# HMC1001_module.net
KiCad netlist of a schematic drawn in Altium Designer
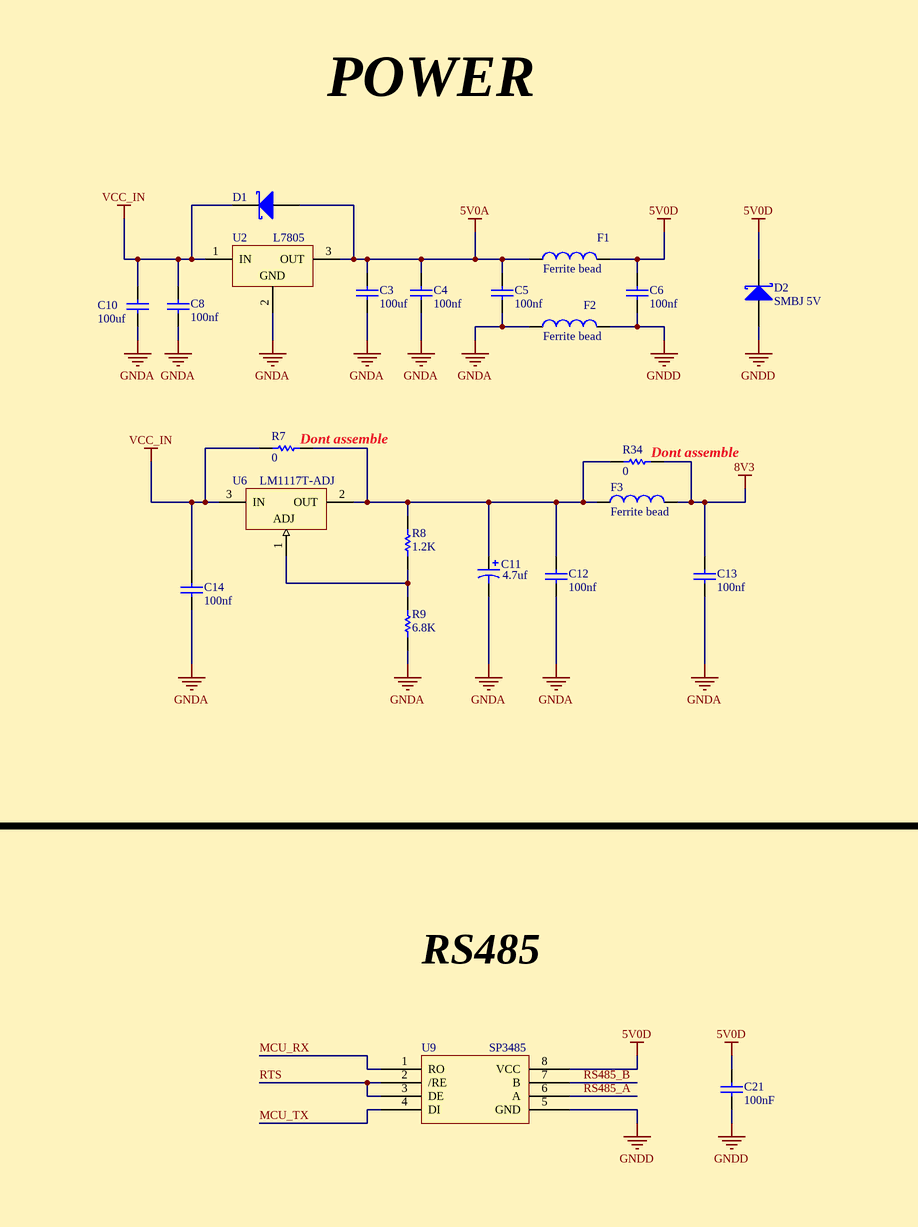
[diagram p0: HMC1001_module.SchDoc, top left]
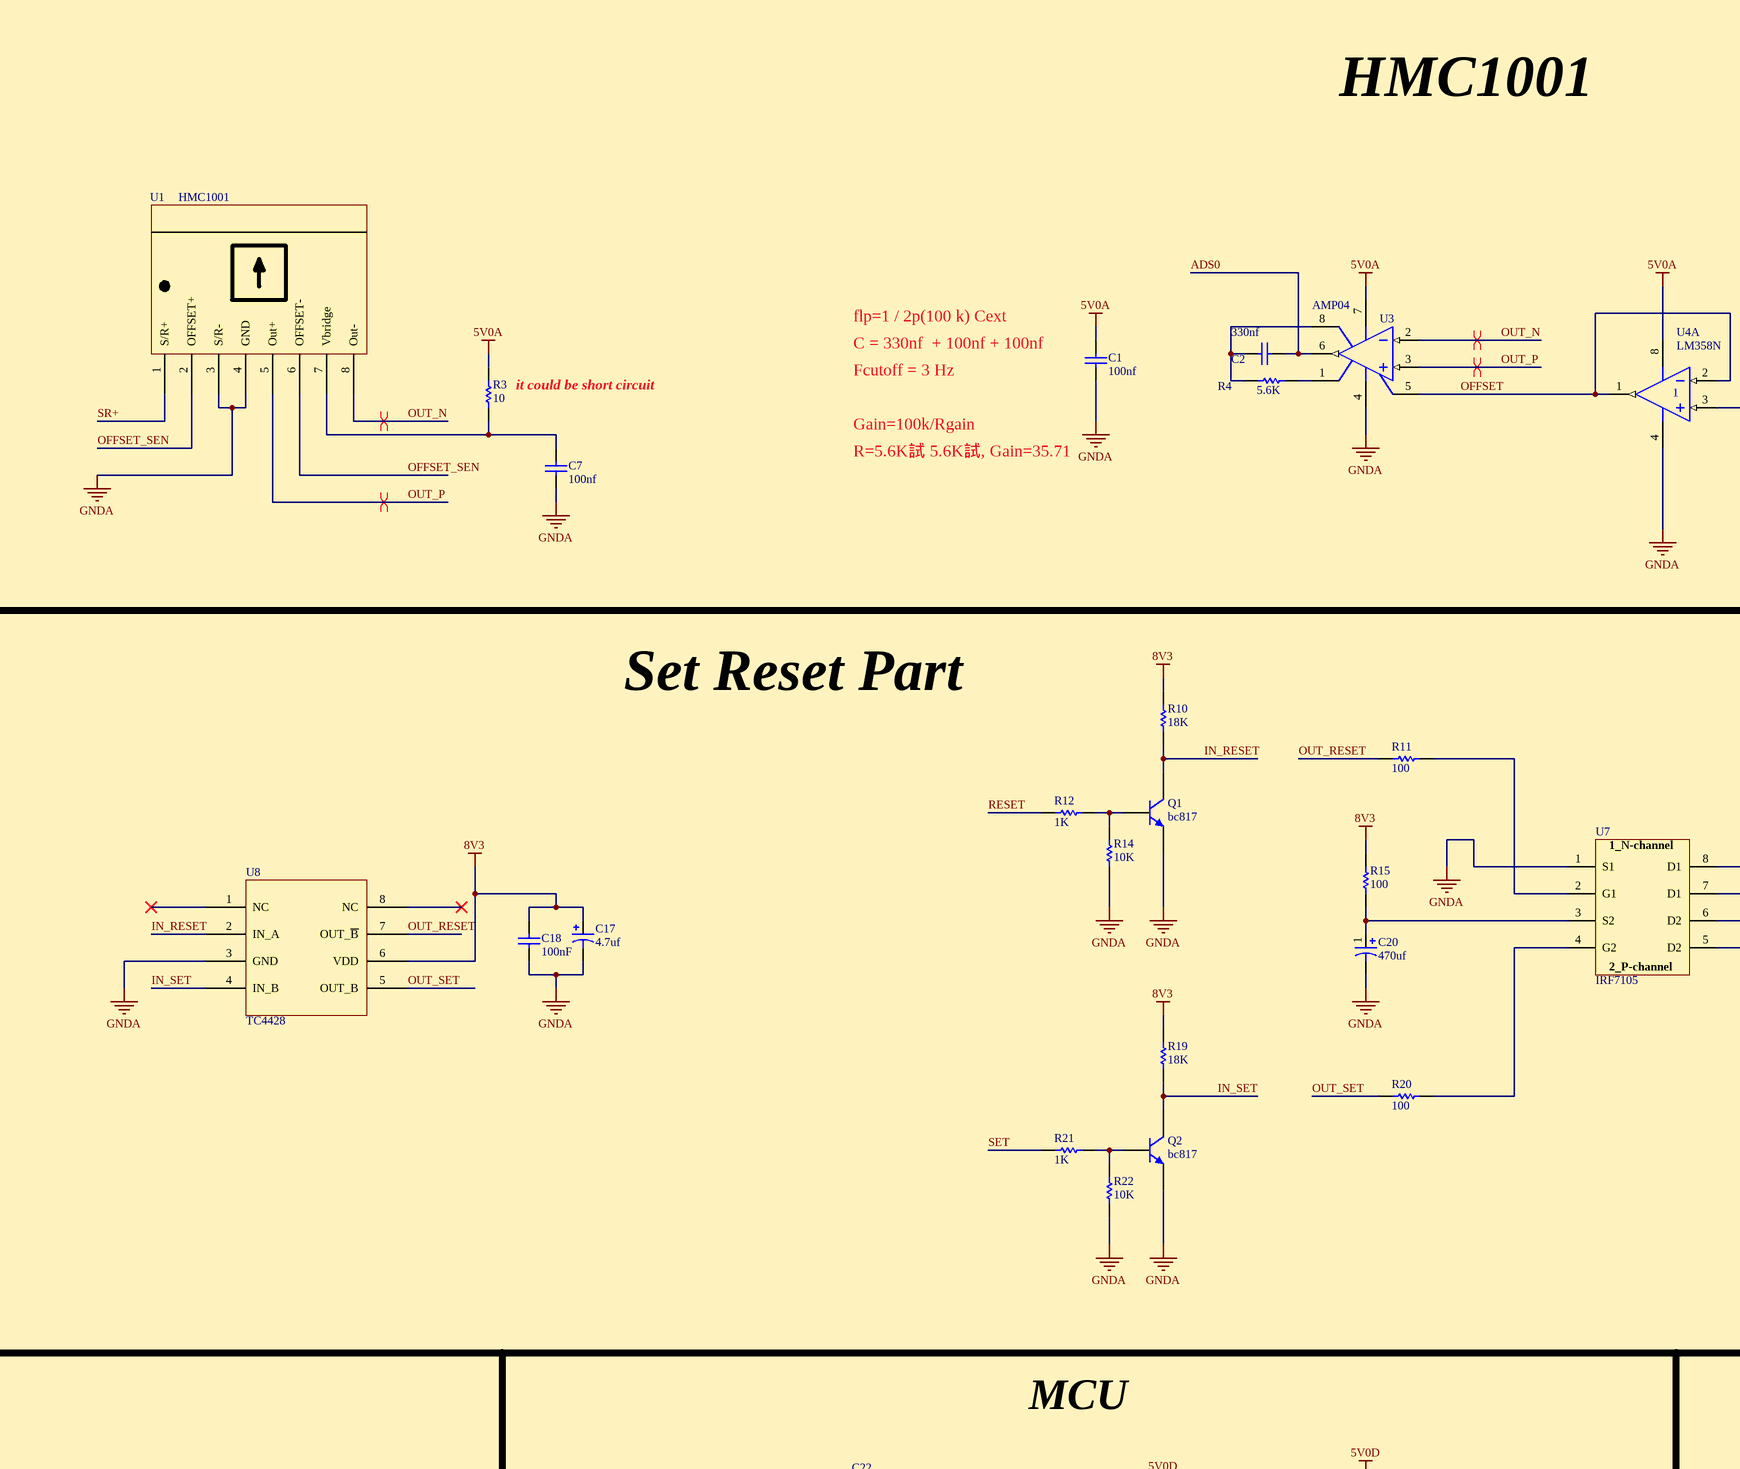
[diagram p1: HMC1001_module.SchDoc, top middle]
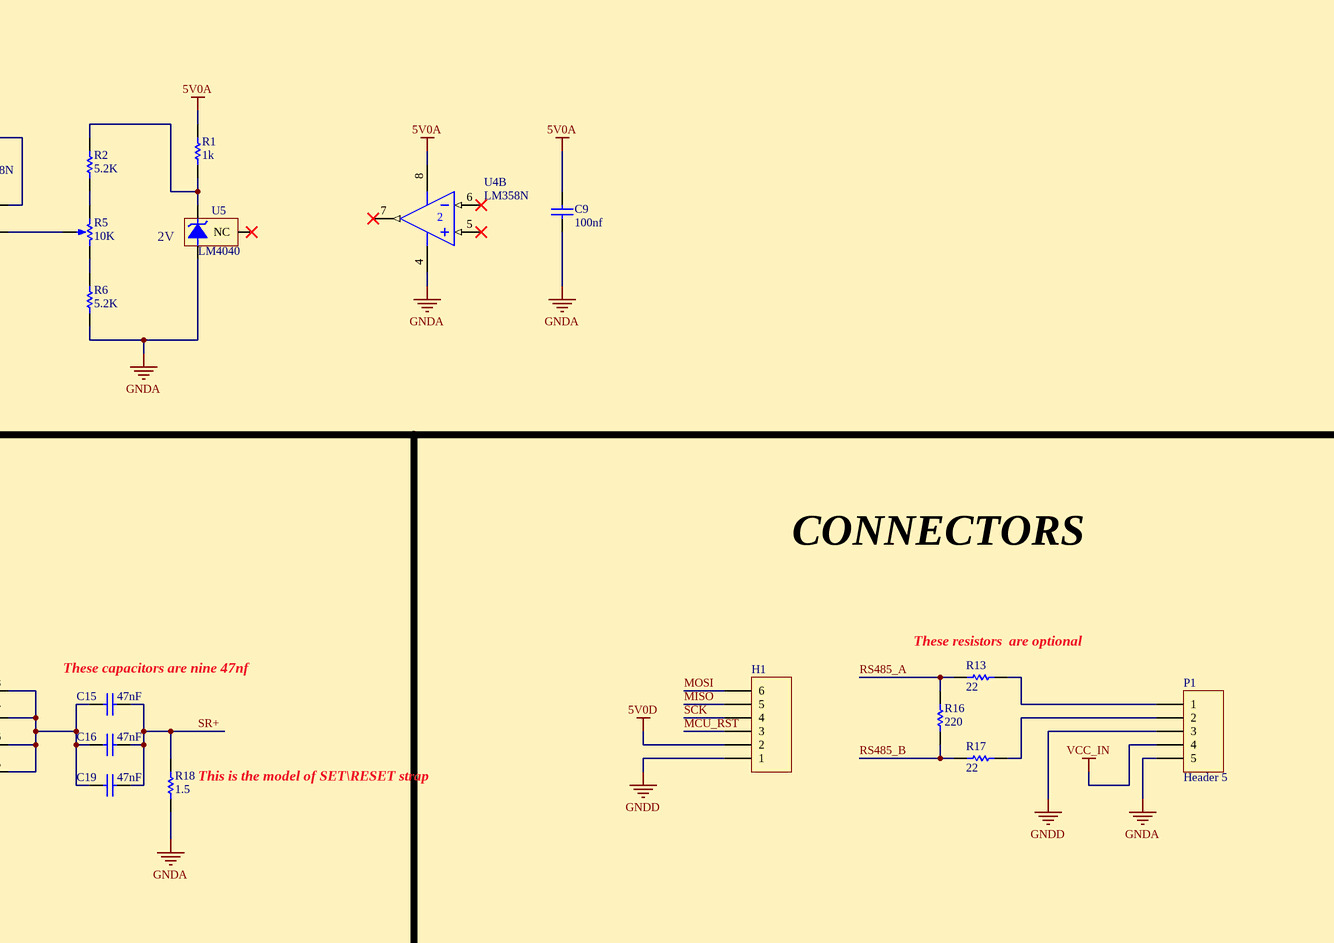
[diagram p2: HMC1001_module.SchDoc, top right]
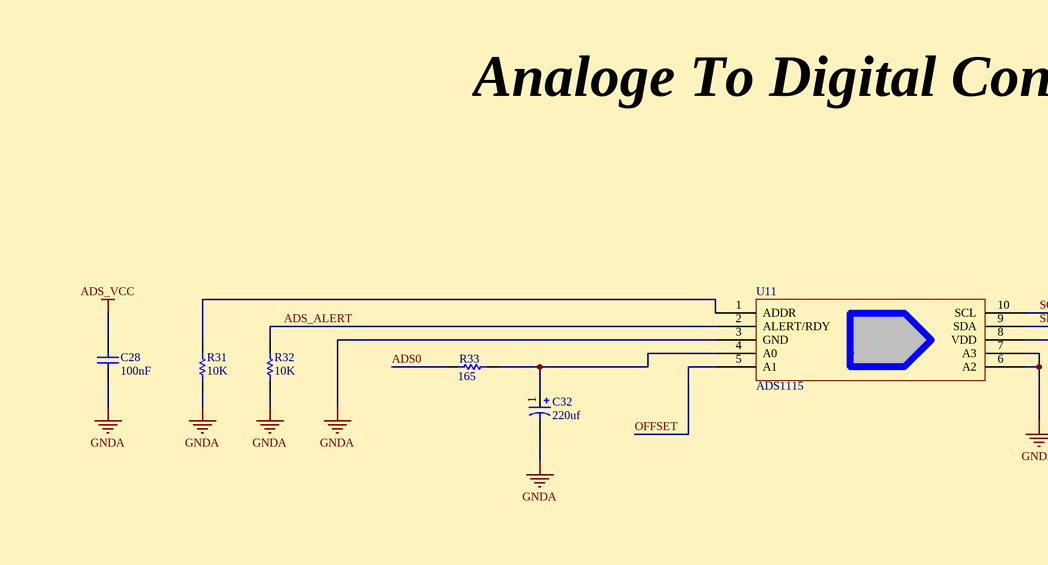
[diagram p3: HMC1001_module.SchDoc, bottom left]
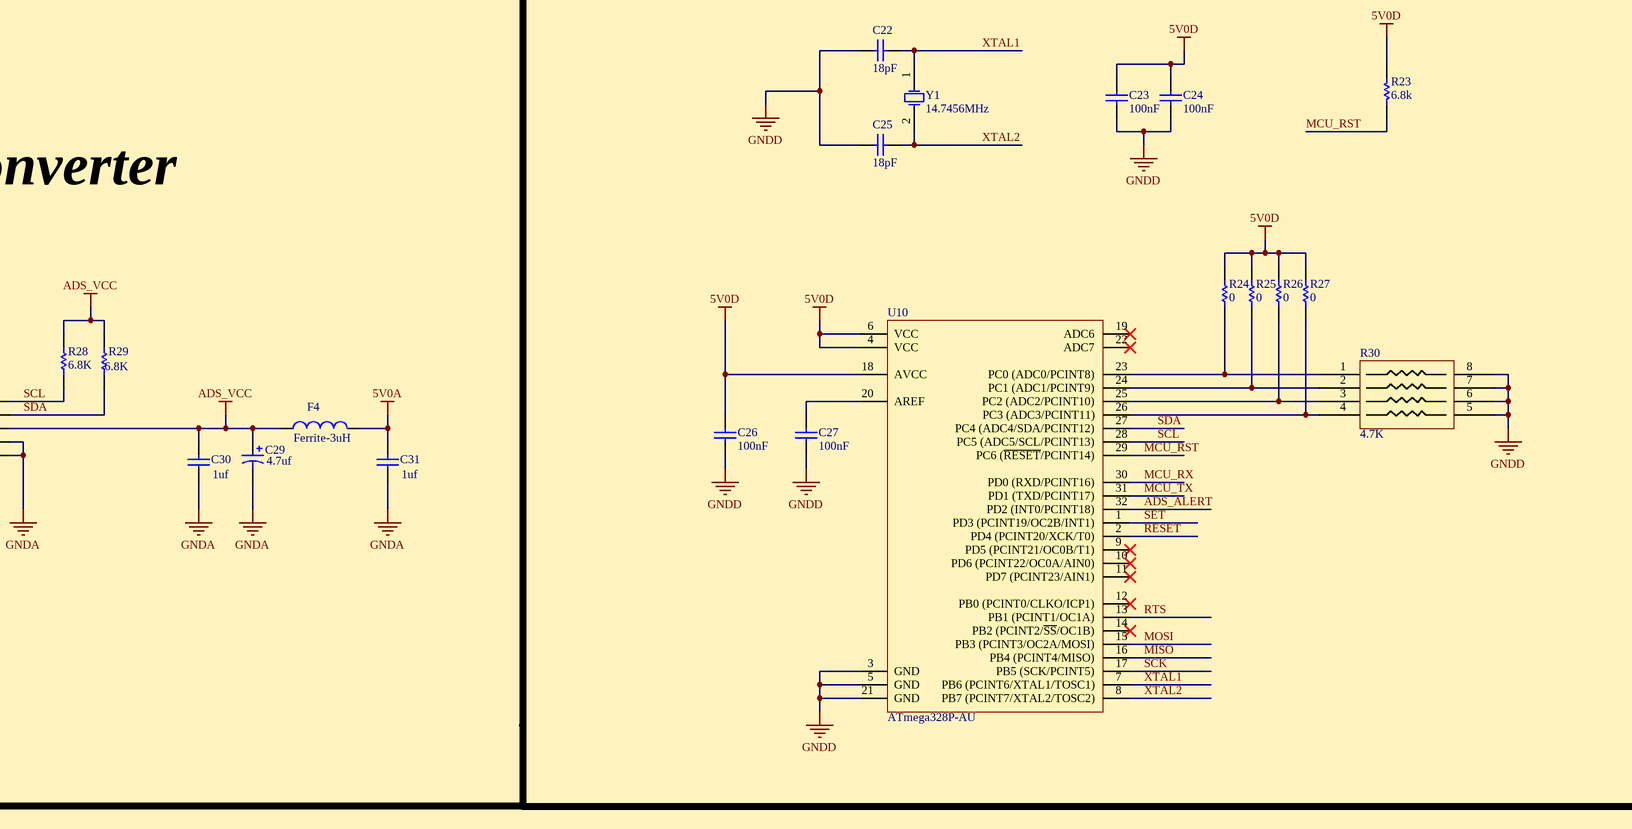
[diagram p4: HMC1001_module.SchDoc, bottom middle]
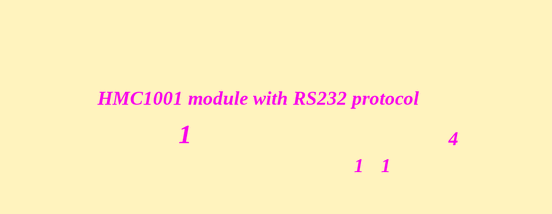
[diagram p5: HMC1001_module.SchDoc, bottom right]

(export (version "E")
  (design (tool "Eeschema 10.0.6"))
  (components
    (comp (ref "C1")
      (value "100nf")
      (footprint "C0805")
      (description "Capacitor")
      (fields (field (name "PUBLISHER") "Altium Limited"))
      (libsource (lib "Miscellaneous Devices") (part "Cap"))
    )
    (comp (ref "C2")
      (value "330nf")
      (footprint "C0805")
      (description "Capacitor")
      (fields (field (name "PUBLISHER") "Altium Limited"))
      (libsource (lib "Library") (part "Cap"))
    )
    (comp (ref "C3")
      (value "100uf")
      (footprint "C1206")
      (description "Capacitor, 1206")
      (fields (field (name "PUBLISHER") "Altium Limited"))
      (libsource (lib "Miscellaneous Devices") (part "Cap"))
    )
    (comp (ref "C4")
      (value "100nf")
      (footprint "C0805")
      (description "Capacitor, 1206")
      (fields (field (name "PUBLISHER") "Altium Limited"))
      (libsource (lib "Miscellaneous Devices") (part "Cap"))
    )
    (comp (ref "C5")
      (value "100nf")
      (footprint "C0805")
      (description "Capacitor, 1206")
      (fields (field (name "PUBLISHER") "Altium Limited"))
      (libsource (lib "Miscellaneous Devices") (part "Cap"))
    )
    (comp (ref "C6")
      (value "100nf")
      (footprint "C0805")
      (description "Capacitor, 1206")
      (fields (field (name "PUBLISHER") "Altium Limited"))
      (libsource (lib "Miscellaneous Devices") (part "Cap"))
    )
    (comp (ref "C7")
      (value "100nf")
      (footprint "C0805")
      (description "Capacitor")
      (fields (field (name "PUBLISHER") "Altium Limited"))
      (libsource (lib "Miscellaneous Devices") (part "Cap"))
    )
    (comp (ref "C8")
      (value "100nf")
      (footprint "C0805")
      (description "Capacitor, 1206")
      (fields (field (name "PUBLISHER") "Altium Limited"))
      (libsource (lib "Miscellaneous Devices") (part "Cap"))
    )
    (comp (ref "C9")
      (value "100nf")
      (footprint "C0805")
      (description "Capacitor")
      (fields (field (name "PUBLISHER") "Altium Limited"))
      (libsource (lib "Miscellaneous Devices") (part "Cap"))
    )
    (comp (ref "C10")
      (value "100uf")
      (footprint "C1206")
      (description "Capacitor, 1206")
      (fields (field (name "PUBLISHER") "Altium Limited"))
      (libsource (lib "Miscellaneous Devices") (part "Cap"))
    )
    (comp (ref "C11")
      (value "4.7uf")
      (footprint "cap_smd_a")
      (description "Polarized Capacitor (Radial)")
      (fields (field (name "PUBLISHER") "Altium Limited"))
      (libsource (lib "Miscellaneous Devices") (part "Cap Pol1"))
    )
    (comp (ref "C12")
      (value "100nf")
      (footprint "C0805")
      (description "Capacitor")
      (fields (field (name "PUBLISHER") "Altium Limited"))
      (libsource (lib "Miscellaneous Devices") (part "Cap"))
    )
    (comp (ref "C13")
      (value "100nf")
      (footprint "C0805")
      (description "Capacitor")
      (fields (field (name "PUBLISHER") "Altium Limited"))
      (libsource (lib "Miscellaneous Devices") (part "Cap"))
    )
    (comp (ref "C14")
      (value "100nf")
      (footprint "C0805")
      (description "Capacitor")
      (fields (field (name "PUBLISHER") "Altium Limited"))
      (libsource (lib "Miscellaneous Devices") (part "Cap"))
    )
    (comp (ref "C15")
      (value "47nF")
      (footprint "C1206")
      (description "Capacitor")
      (fields (field (name "PUBLISHER") "Altium Limited"))
      (libsource (lib "") (part "Cap_1"))
    )
    (comp (ref "C16")
      (value "47nF")
      (footprint "C1206")
      (description "Capacitor")
      (fields (field (name "PUBLISHER") "Altium Limited"))
      (libsource (lib "") (part "Cap_1"))
    )
    (comp (ref "C17")
      (value "4.7uf")
      (footprint "cap_smd_a")
      (description "Polarized Capacitor (Radial)")
      (fields (field (name "PUBLISHER") "Altium Limited"))
      (libsource (lib "") (part "Cap Pol1_2"))
    )
    (comp (ref "C18")
      (value "100nF")
      (footprint "C0805")
      (description "Capacitor")
      (fields (field (name "PUBLISHER") "Altium Limited"))
      (libsource (lib "Miscellaneous Devices") (part "Cap"))
    )
    (comp (ref "C19")
      (value "47nF")
      (footprint "C1206")
      (description "Capacitor")
      (fields (field (name "PUBLISHER") "Altium Limited"))
      (libsource (lib "") (part "Cap_1"))
    )
    (comp (ref "C20")
      (value "470uf")
      (footprint "cap_smd_d")
      (description "TAN CAP D SIZE")
      (fields (field (name "PUBLISHER") "Altium Limited"))
      (libsource (lib "") (part "Cap Pol1_1"))
    )
    (comp (ref "C21")
      (value "100nF")
      (footprint "C0805")
      (description "Capacitor")
      (fields (field (name "PUBLISHER") "Altium Limited"))
      (libsource (lib "Miscellaneous Devices") (part "Cap"))
    )
    (comp (ref "C22")
      (value "18pF")
      (footprint "C0805")
      (description "Capacitor")
      (fields (field (name "PUBLISHER") "Altium Limited"))
      (libsource (lib "Miscellaneous Devices") (part "Cap"))
    )
    (comp (ref "C23")
      (value "100nF")
      (footprint "C0805")
      (description "Capacitor")
      (fields (field (name "PUBLISHER") "Altium Limited"))
      (libsource (lib "Miscellaneous Devices") (part "Cap"))
    )
    (comp (ref "C24")
      (value "100nF")
      (footprint "C0805")
      (description "Capacitor")
      (fields (field (name "PUBLISHER") "Altium Limited"))
      (libsource (lib "Miscellaneous Devices") (part "Cap"))
    )
    (comp (ref "C25")
      (value "18pF")
      (footprint "C0805")
      (description "Capacitor")
      (fields (field (name "PUBLISHER") "Altium Limited"))
      (libsource (lib "Miscellaneous Devices") (part "Cap"))
    )
    (comp (ref "C26")
      (value "100nF")
      (footprint "C0805")
      (description "Capacitor")
      (fields (field (name "PUBLISHER") "Altium Limited"))
      (libsource (lib "Miscellaneous Devices") (part "Cap"))
    )
    (comp (ref "C27")
      (value "100nF")
      (footprint "C0805")
      (description "Capacitor")
      (fields (field (name "PUBLISHER") "Altium Limited"))
      (libsource (lib "Miscellaneous Devices") (part "Cap"))
    )
    (comp (ref "C28")
      (value "100nF")
      (footprint "C0805")
      (description "Capacitor")
      (fields (field (name "PUBLISHER") "Altium Limited"))
      (libsource (lib "Miscellaneous Devices") (part "Cap"))
    )
    (comp (ref "C29")
      (value "4.7uf")
      (footprint "CAP_SMD_A")
      (description "Tantalium Capacitor")
      (fields (field (name "PUBLISHER") "Altium Limited"))
      (libsource (lib "Library") (part "Cap Pol"))
    )
    (comp (ref "C30")
      (value "1uf")
      (footprint "C0805")
      (description "Capacitor, 1206")
      (fields (field (name "PUBLISHER") "Altium Limited"))
      (libsource (lib "Library") (part "Cap"))
    )
    (comp (ref "C31")
      (value "1uf")
      (footprint "C0805")
      (description "Capacitor, 1206")
      (fields (field (name "PUBLISHER") "Altium Limited"))
      (libsource (lib "Library") (part "Cap"))
    )
    (comp (ref "C32")
      (value "220uf")
      (footprint "cap_smd_d")
      (description "TAN CAP D SIZE")
      (fields (field (name "PUBLISHER") "Altium Limited"))
      (libsource (lib "") (part "Cap Pol1_1"))
    )
    (comp (ref "D1")
      (value "D Schottky")
      (footprint "ZENER")
      (description "Schottky Diode, 1N4148")
      (fields (field (name "PUBLISHER") "Altium Limited"))
      (libsource (lib "Miscellaneous Devices") (part "D Schottky"))
    )
    (comp (ref "D2")
      (value "SMBJ 5V")
      (footprint "TVS")
      (description "Schottky Rectifier")
      (fields (field (name "PUBLISHER") "Altium Limited"))
      (libsource (lib "Miscellaneous Devices") (part "Diode 18TQ045"))
    )
    (comp (ref "F1")
      (value "Ferrite bead")
      (footprint "1206")
      (description "Ferrite bead, 1206")
      (fields (field (name "PUBLISHER") "Altium Limited"))
      (libsource (lib "Miscellaneous Devices") (part "Inductor"))
    )
    (comp (ref "F2")
      (value "Ferrite bead")
      (footprint "1206")
      (description "Ferrite bead, 1206")
      (fields (field (name "PUBLISHER") "Altium Limited"))
      (libsource (lib "Miscellaneous Devices") (part "Inductor"))
    )
    (comp (ref "F3")
      (value "Ferrite bead")
      (footprint "1206")
      (description "Ferrite bead, 1206")
      (fields (field (name "PUBLISHER") "Altium Limited"))
      (libsource (lib "Miscellaneous Devices") (part "Inductor"))
    )
    (comp (ref "F4")
      (value "Ferrite-3uH")
      (footprint "1206")
      (description "Inductor")
      (fields (field (name "PUBLISHER") "Altium Limited"))
      (libsource (lib "Miscellaneous Devices") (part "Inductor"))
    )
    (comp (ref "H1")
      (value "White SMD Connector 6pin")
      (footprint "SH_6pin_B")
      (fields (field (name "PUBLISHER") "Altium Limited"))
      (libsource (lib "Miscellaneous Connectors") (part "Header 6"))
    )
    (comp (ref "P1")
      (value "Header 5")
      (footprint "HDR_M_1x5")
      (description "Header, 5-Pin")
      (fields (field (name "PUBLISHER") "Altium Limited"))
      (libsource (lib "Miscellaneous Connectors") (part "Header 5"))
    )
    (comp (ref "Q1")
      (value "bc817")
      (footprint "sot-23")
      (description "NPN General Purpose Amplifier")
      (fields (field (name "PUBLISHER") "Altium Limited"))
      (libsource (lib "Miscellaneous Devices") (part "2N3904"))
    )
    (comp (ref "Q2")
      (value "bc817")
      (footprint "sot-23")
      (description "NPN General Purpose Amplifier")
      (fields (field (name "PUBLISHER") "Altium Limited"))
      (libsource (lib "Miscellaneous Devices") (part "2N3904"))
    )
    (comp (ref "R1")
      (value "1k")
      (footprint "0805")
      (description "Resistor")
      (fields (field (name "PUBLISHER") "Seyed Razi Vesali") (field (name "EMAIL") "razi.vesali@gmail.com"))
      (libsource (lib "resistor1") (part "Resistor"))
    )
    (comp (ref "R2")
      (value "5.2K")
      (footprint "0805")
      (description "General Resistor")
      (fields (field (name "PUBLISHER") "Altium Limited"))
      (libsource (lib "Library") (part "Resistor"))
    )
    (comp (ref "R3")
      (value "10")
      (footprint "0805")
      (description "Resistor")
      (fields (field (name "PUBLISHER") "Seyed Razi Vesali") (field (name "EMAIL") "razi.vesali@gmail.com"))
      (libsource (lib "resistor1") (part "Resistor"))
    )
    (comp (ref "R4")
      (value "5.6K")
      (footprint "0805")
      (description "General Resistor")
      (fields (field (name "PUBLISHER") "Altium Limited"))
      (libsource (lib "Library") (part "Resistor"))
    )
    (comp (ref "R5")
      (value "10K")
      (footprint "POT_3296w")
      (description "Potentiometer")
      (fields (field (name "Comment") "RPot") (field (name "PUBLISHER") "Altium Limited"))
      (libsource (lib "Miscellaneous Devices") (part "RPot"))
    )
    (comp (ref "R6")
      (value "5.2K")
      (footprint "0805")
      (description "General Resistor")
      (fields (field (name "PUBLISHER") "Altium Limited"))
      (libsource (lib "Library") (part "Resistor"))
    )
    (comp (ref "R7")
      (value "0")
      (footprint "0603")
      (description "Resistor")
      (fields (field (name "PUBLISHER") "Seyed Razi Vesali") (field (name "EMAIL") "razi.vesali@gmail.com"))
      (libsource (lib "resistor1") (part "Resistor"))
    )
    (comp (ref "R8")
      (value "1.2K")
      (footprint "0805")
      (description "Resistor")
      (fields (field (name "PUBLISHER") "Seyed Razi Vesali") (field (name "EMAIL") "razi.vesali@gmail.com"))
      (libsource (lib "resistor1") (part "Resistor"))
    )
    (comp (ref "R9")
      (value "6.8K")
      (footprint "0805")
      (description "Resistor")
      (fields (field (name "PUBLISHER") "Seyed Razi Vesali") (field (name "EMAIL") "razi.vesali@gmail.com"))
      (libsource (lib "resistor1") (part "Resistor"))
    )
    (comp (ref "R10")
      (value "18K")
      (footprint "0805")
      (description "Resistor")
      (fields (field (name "PUBLISHER") "Altium Limited"))
      (libsource (lib "Miscellaneous Devices") (part "Res1"))
    )
    (comp (ref "R11")
      (value "100")
      (footprint "0805")
      (description "Resistor")
      (fields (field (name "PUBLISHER") "Altium Limited"))
      (libsource (lib "Miscellaneous Devices") (part "Res1"))
    )
    (comp (ref "R12")
      (value "1K")
      (footprint "0805")
      (description "Resistor")
      (fields (field (name "PUBLISHER") "Altium Limited"))
      (libsource (lib "Miscellaneous Devices") (part "Res1"))
    )
    (comp (ref "R13")
      (value "22")
      (footprint "0805")
      (description "Resistor")
      (fields (field (name "PUBLISHER") "Altium Limited"))
      (libsource (lib "Miscellaneous Devices") (part "Res1"))
    )
    (comp (ref "R14")
      (value "10K")
      (footprint "0805")
      (description "Resistor")
      (fields (field (name "PUBLISHER") "Altium Limited"))
      (libsource (lib "Miscellaneous Devices") (part "Res1"))
    )
    (comp (ref "R15")
      (value "100")
      (footprint "0805")
      (description "Resistor")
      (fields (field (name "PUBLISHER") "Altium Limited"))
      (libsource (lib "Miscellaneous Devices") (part "Res1"))
    )
    (comp (ref "R16")
      (value "220")
      (footprint "0805")
      (description "Resistor")
      (fields (field (name "PUBLISHER") "Altium Limited"))
      (libsource (lib "Miscellaneous Devices") (part "Res1"))
    )
    (comp (ref "R17")
      (value "22")
      (footprint "0805")
      (description "Resistor")
      (fields (field (name "PUBLISHER") "Altium Limited"))
      (libsource (lib "Miscellaneous Devices") (part "Res1"))
    )
    (comp (ref "R18")
      (value "1.5")
      (footprint "0805")
      (description "Resistor")
      (fields (field (name "PUBLISHER") "Altium Limited"))
      (libsource (lib "Miscellaneous Devices") (part "Res1"))
    )
    (comp (ref "R19")
      (value "18K")
      (footprint "0805")
      (description "Resistor")
      (fields (field (name "PUBLISHER") "Altium Limited"))
      (libsource (lib "Miscellaneous Devices") (part "Res1"))
    )
    (comp (ref "R20")
      (value "100")
      (footprint "0805")
      (description "Resistor")
      (fields (field (name "PUBLISHER") "Altium Limited"))
      (libsource (lib "Miscellaneous Devices") (part "Res1"))
    )
    (comp (ref "R21")
      (value "1K")
      (footprint "0805")
      (description "Resistor")
      (fields (field (name "PUBLISHER") "Altium Limited"))
      (libsource (lib "Miscellaneous Devices") (part "Res1"))
    )
    (comp (ref "R22")
      (value "10K")
      (footprint "0805")
      (description "Resistor")
      (fields (field (name "PUBLISHER") "Altium Limited"))
      (libsource (lib "Miscellaneous Devices") (part "Res1"))
    )
    (comp (ref "R23")
      (value "6.8k")
      (footprint "0805")
      (description "Resistor, 6.8k")
      (fields (field (name "PUBLISHER") "Altium Limited"))
      (libsource (lib "Miscellaneous Devices") (part "Res1"))
    )
    (comp (ref "R24")
      (value "0")
      (footprint "0603")
      (description "Resistor, 6.8k")
      (fields (field (name "PUBLISHER") "Altium Limited"))
      (libsource (lib "Miscellaneous Devices") (part "Res1"))
    )
    (comp (ref "R25")
      (value "0")
      (footprint "0603")
      (description "Resistor, 6.8k")
      (fields (field (name "PUBLISHER") "Altium Limited"))
      (libsource (lib "Miscellaneous Devices") (part "Res1"))
    )
    (comp (ref "R26")
      (value "0")
      (footprint "0603")
      (description "Resistor, 6.8k")
      (fields (field (name "PUBLISHER") "Altium Limited"))
      (libsource (lib "Miscellaneous Devices") (part "Res1"))
    )
    (comp (ref "R27")
      (value "0")
      (footprint "0603")
      (description "Resistor, 6.8k")
      (fields (field (name "PUBLISHER") "Altium Limited"))
      (libsource (lib "Miscellaneous Devices") (part "Res1"))
    )
    (comp (ref "R28")
      (value "6.8K")
      (footprint "0805")
      (description "General Resistor")
      (fields (field (name "PUBLISHER") "Altium Limited"))
      (libsource (lib "Library") (part "Resistor"))
    )
    (comp (ref "R29")
      (value "6.8K")
      (footprint "0805")
      (description "General Resistor")
      (fields (field (name "PUBLISHER") "Altium Limited"))
      (libsource (lib "Library") (part "Resistor"))
    )
    (comp (ref "R30")
      (value "4.7K")
      (footprint "RP0603X4")
      (libsource (lib "RES_ARRAY_4") (part "RES_ARRAY_4"))
    )
    (comp (ref "R31")
      (value "10K")
      (footprint "0805")
      (description "General Resistor")
      (fields (field (name "PUBLISHER") "Altium Limited"))
      (libsource (lib "Library") (part "Resistor"))
    )
    (comp (ref "R32")
      (value "10K")
      (footprint "0805")
      (description "General Resistor")
      (fields (field (name "PUBLISHER") "Altium Limited"))
      (libsource (lib "Library") (part "Resistor"))
    )
    (comp (ref "R33")
      (value "165")
      (footprint "0805")
      (description "General Resistor")
      (fields (field (name "PUBLISHER") "Altium Limited"))
      (libsource (lib "Library") (part "Resistor"))
    )
    (comp (ref "R34")
      (value "0")
      (footprint "0603")
      (description "Resistor")
      (fields (field (name "PUBLISHER") "Seyed Razi Vesali") (field (name "EMAIL") "razi.vesali@gmail.com"))
      (libsource (lib "resistor1") (part "Resistor"))
    )
    (comp (ref "U1") (value "HMC1001") (footprint "HMC1001") (libsource (lib "Library") (part "HMC1001")))
    (comp (ref "U2")
      (value "L7805")
      (footprint "DPAK")
      (description "Positive Voltage Regulator")
      (fields (field (name "PUBLISHER") "Altium Limited"))
      (libsource (lib "ST Power Mgt Voltage Regulator") (part "L7805CD2T"))
    )
    (comp (ref "U3")
      (value "AMP04")
      (footprint "sop8")
      (fields (field (name "PUBLISHER") "Altium Limited"))
      (libsource (lib "Miscellaneous Devices") (part "Op Amp"))
    )
    (comp (ref "U4")
      (value "LM358N")
      (footprint "sop8")
      (description "Dual Low-Power Operational Amplifier")
      (fields (field (name "PUBLISHER") "Altium Limited"))
      (libsource (lib "Motorola Amplifier Operational Amplifier") (part "LM358N"))
    )
    (comp (ref "U5")
      (value "LM4040")
      (footprint "sot-23")
      (description "Precision Micropower Shunt Voltage Reference, 3-pin SOT-23")
      (fields
        (field (name "PARTNUMBER") "LM4040DIM3-10.0")
        (field (name "MANUFACTURER") "National Semiconductor")
        (field (name "PUBLISHER") "Altium Limited")
      )
      (libsource (lib "final_sensor_sch_lib") (part "LM4040"))
    )
    (comp (ref "U6")
      (value "LM1117T-ADJ")
      (footprint "DPAK")
      (description "800mA Low-Dropout Linear Regulator")
      (fields
        (field (name "MANUFACTURER") "National Semiconductor")
        (field (name "DIGIKEYPARTNUMBER") "LM1117T-ADJ-ND")
        (field (name "PUBLISHER") "Altium Limited")
      )
      (libsource (lib "NSC LDO") (part "LM1117T-ADJ"))
    )
    (comp (ref "U7") (value "IRF7105") (footprint "sop8") (libsource (lib "irf7106") (part "IRF7106")))
    (comp (ref "U8") (value "TC4428") (footprint "sop8") (libsource (lib "tc4428") (part "TC4428")))
    (comp (ref "U9") (value "SP3485") (footprint "SOP8") (libsource (lib "Schlib_RS485") (part "rs485")))
    (comp (ref "U10")
      (value "ATmega328P-AU")
      (footprint "32A_L")
      (fields (field (name "PUBLISHER") "Altium Limited"))
      (libsource (lib "Library") (part "ATmega328P-AU"))
    )
    (comp (ref "U11") (value "ADS1115") (footprint "TSSOP10_N") (libsource (lib "Library") (part "ADS1115")))
    (comp (ref "Y1")
      (value "14.7456MHz")
      (footprint "XTALL")
      (description "Crystal Oscillator, 14.7456KHz")
      (fields (field (name "PUBLISHER") "Altium Limited"))
      (libsource (lib "Miscellaneous Devices") (part "XTAL"))
    )
  )
  (nets
    (net (code "1") (name "/ADS0") (class "Default")
      (node (ref "C2") (pin "1") (pinfunction "1_1") (pintype "passive"))
      (node (ref "R33") (pin "1") (pinfunction "1_1") (pintype "passive"))
      (node (ref "U3") (pin "6") (pinfunction "OUT_6") (pintype "output"))
    )
    (net (code "2") (name "/ADS_ALERT") (class "Default")
      (node (ref "R32") (pin "2") (pinfunction "2_2") (pintype "passive"))
      (node (ref "U10") (pin "32") (pinfunction "PD2_(INT0/PCINT18)_32") (pintype "passive"))
      (node (ref "U11") (pin "2") (pinfunction "ALERT/RDY_2") (pintype "passive"))
    )
    (net (code "3") (name "/IN_RESET") (class "Default")
      (node (ref "Q1") (pin "3") (pinfunction "C_3") (pintype "passive"))
      (node (ref "R10") (pin "1") (pinfunction "1_1") (pintype "passive"))
      (node (ref "U8") (pin "2") (pinfunction "IN_A_2") (pintype "passive"))
    )
    (net (code "4") (name "/IN_SET") (class "Default")
      (node (ref "Q2") (pin "3") (pinfunction "C_3") (pintype "passive"))
      (node (ref "R19") (pin "1") (pinfunction "1_1") (pintype "passive"))
      (node (ref "U8") (pin "4") (pinfunction "IN_B_4") (pintype "passive"))
    )
    (net (code "5") (name "/MCU_RST") (class "Default")
      (node (ref "H1") (pin "3") (pinfunction "3_3") (pintype "passive"))
      (node (ref "R23") (pin "2") (pinfunction "2_2") (pintype "passive"))
      (node (ref "U10") (pin "29") (pinfunction "PC6_(~{RESET}/PCINT14)_29") (pintype "passive"))
    )
    (net (code "6") (name "/MCU_RX") (class "Default")
      (node (ref "U10") (pin "30") (pinfunction "PD0_(RXD/PCINT16)_30") (pintype "passive"))
      (node (ref "U9") (pin "1") (pinfunction "RO_1") (pintype "passive"))
    )
    (net (code "7") (name "/MCU_TX") (class "Default")
      (node (ref "U10") (pin "31") (pinfunction "PD1_(TXD/PCINT17)_31") (pintype "passive"))
      (node (ref "U9") (pin "4") (pinfunction "DI_4") (pintype "passive"))
    )
    (net (code "8") (name "/MISO") (class "Default")
      (node (ref "H1") (pin "5") (pinfunction "5_5") (pintype "passive"))
      (node (ref "U10") (pin "16") (pinfunction "PB4_(PCINT4/MISO)_16") (pintype "passive"))
    )
    (net (code "9") (name "/MOSI") (class "Default")
      (node (ref "H1") (pin "6") (pinfunction "6_6") (pintype "passive"))
      (node (ref "U10") (pin "15") (pinfunction "PB3_(PCINT3/OC2A/MOSI)_15") (pintype "passive"))
    )
    (net (code "10") (name "/OFFSET") (class "Default")
      (node (ref "U11") (pin "5") (pinfunction "A1_5") (pintype "passive"))
      (node (ref "U3") (pin "5") (pinfunction "OS_NUL_5") (pintype "passive"))
      (node (ref "U4") (pin "1") (pinfunction "OUT_1") (pintype "output"))
      (node (ref "U4") (pin "2") (pinfunction "IN-_2") (pintype "input"))
    )
    (net (code "11") (name "/OFFSET_SEN") (class "Default")
      (node (ref "U1") (pin "2") (pinfunction "OFFSET+_2") (pintype "passive"))
      (node (ref "U1") (pin "6") (pinfunction "OFFSET-_6") (pintype "passive"))
    )
    (net (code "12") (name "/OUT_N") (class "Default")
      (node (ref "U1") (pin "8") (pinfunction "Out-_8") (pintype "passive"))
      (node (ref "U3") (pin "2") (pinfunction "IN-_2") (pintype "input"))
    )
    (net (code "13") (name "/OUT_P") (class "Default")
      (node (ref "U1") (pin "5") (pinfunction "Out+_5") (pintype "passive"))
      (node (ref "U3") (pin "3") (pinfunction "IN+_3") (pintype "input"))
    )
    (net (code "14") (name "/OUT_RESET") (class "Default")
      (node (ref "R11") (pin "2") (pinfunction "2_2") (pintype "passive"))
      (node (ref "U8") (pin "7") (pinfunction "OUT_~{B}_7") (pintype "passive"))
    )
    (net (code "15") (name "/OUT_SET") (class "Default")
      (node (ref "R20") (pin "2") (pinfunction "2_2") (pintype "passive"))
      (node (ref "U8") (pin "5") (pinfunction "OUT_B_5") (pintype "passive"))
    )
    (net (code "16") (name "/RESET") (class "Default")
      (node (ref "R12") (pin "1") (pinfunction "1_1") (pintype "passive"))
      (node (ref "U10") (pin "2") (pinfunction "PD4_(PCINT20/XCK/T0)_2") (pintype "passive"))
    )
    (net (code "17") (name "/RS485_A") (class "Default")
      (node (ref "R13") (pin "1") (pinfunction "1_1") (pintype "passive"))
      (node (ref "R16") (pin "1") (pinfunction "1_1") (pintype "passive"))
      (node (ref "U9") (pin "6") (pinfunction "A_6") (pintype "passive"))
    )
    (net (code "18") (name "/RS485_B") (class "Default")
      (node (ref "R16") (pin "2") (pinfunction "2_2") (pintype "passive"))
      (node (ref "R17") (pin "1") (pinfunction "1_1") (pintype "passive"))
      (node (ref "U9") (pin "7") (pinfunction "B_7") (pintype "passive"))
    )
    (net (code "19") (name "/RTS") (class "Default")
      (node (ref "U10") (pin "13") (pinfunction "PB1_(PCINT1/OC1A)_13") (pintype "passive"))
      (node (ref "U9") (pin "2") (pinfunction "/RE_2") (pintype "passive"))
      (node (ref "U9") (pin "3") (pinfunction "DE_3") (pintype "passive"))
    )
    (net (code "20") (name "/SCK") (class "Default")
      (node (ref "H1") (pin "4") (pinfunction "4_4") (pintype "passive"))
      (node (ref "U10") (pin "17") (pinfunction "PB5_(SCK/PCINT5)_17") (pintype "passive"))
    )
    (net (code "21") (name "/SCL") (class "Default")
      (node (ref "R28") (pin "2") (pinfunction "2_2") (pintype "passive"))
      (node (ref "U10") (pin "28") (pinfunction "PC5_(ADC5/SCL/PCINT13)_28") (pintype "passive"))
      (node (ref "U11") (pin "10") (pinfunction "SCL_10") (pintype "passive"))
    )
    (net (code "22") (name "/SDA") (class "Default")
      (node (ref "R29") (pin "2") (pinfunction "2_2") (pintype "passive"))
      (node (ref "U10") (pin "27") (pinfunction "PC4_(ADC4/SDA/PCINT12)_27") (pintype "passive"))
      (node (ref "U11") (pin "9") (pinfunction "SDA_9") (pintype "passive"))
    )
    (net (code "23") (name "/SET") (class "Default")
      (node (ref "R21") (pin "1") (pinfunction "1_1") (pintype "passive"))
      (node (ref "U10") (pin "1") (pinfunction "PD3_(PCINT19/OC2B/INT1)_1") (pintype "passive"))
    )
    (net (code "24") (name "/SR+") (class "Default")
      (node (ref "C15") (pin "2") (pinfunction "2_2") (pintype "passive"))
      (node (ref "C16") (pin "2") (pinfunction "2_2") (pintype "passive"))
      (node (ref "C19") (pin "2") (pinfunction "2_2") (pintype "passive"))
      (node (ref "R18") (pin "1") (pinfunction "1_1") (pintype "passive"))
      (node (ref "U1") (pin "1") (pinfunction "S/R+_1") (pintype "passive"))
    )
    (net (code "25") (name "/XTAL1") (class "Default")
      (node (ref "C22") (pin "2") (pinfunction "2_2") (pintype "passive"))
      (node (ref "U10") (pin "7") (pinfunction "PB6_(PCINT6/XTAL1/TOSC1)_7") (pintype "passive"))
      (node (ref "Y1") (pin "1") (pinfunction "OSC1_1") (pintype "passive"))
    )
    (net (code "26") (name "/XTAL2") (class "Default")
      (node (ref "C25") (pin "2") (pinfunction "2_2") (pintype "passive"))
      (node (ref "U10") (pin "8") (pinfunction "PB7_(PCINT7/XTAL2/TOSC2)_8") (pintype "passive"))
      (node (ref "Y1") (pin "2") (pinfunction "OSC2_2") (pintype "passive"))
    )
    (net (code "27") (name "5V0A") (class "Default")
      (node (ref "C1") (pin "2") (pinfunction "2_2") (pintype "passive"))
      (node (ref "C3") (pin "2") (pinfunction "2_2") (pintype "passive"))
      (node (ref "C31") (pin "2") (pinfunction "2_2") (pintype "passive"))
      (node (ref "C4") (pin "2") (pinfunction "2_2") (pintype "passive"))
      (node (ref "C5") (pin "2") (pinfunction "2_2") (pintype "passive"))
      (node (ref "C9") (pin "2") (pinfunction "2_2") (pintype "passive"))
      (node (ref "D1") (pin "1") (pinfunction "A_1") (pintype "passive"))
      (node (ref "F1") (pin "1") (pinfunction "1_1") (pintype "passive"))
      (node (ref "F4") (pin "2") (pinfunction "2_2") (pintype "passive"))
      (node (ref "R1") (pin "2") (pinfunction "2_2") (pintype "passive"))
      (node (ref "R3") (pin "2") (pinfunction "2_2") (pintype "passive"))
      (node (ref "U2") (pin "3") (pinfunction "OUT_3") (pintype "power_in"))
      (node (ref "U3") (pin "7") (pinfunction "V+_7") (pintype "power_in"))
      (node (ref "U4") (pin "8") (pinfunction "V+_8") (pintype "power_in"))
    )
    (net (code "28") (name "5V0D") (class "Default")
      (node (ref "C21") (pin "2") (pinfunction "2_2") (pintype "passive"))
      (node (ref "C23") (pin "2") (pinfunction "2_2") (pintype "passive"))
      (node (ref "C24") (pin "2") (pinfunction "2_2") (pintype "passive"))
      (node (ref "C26") (pin "2") (pinfunction "2_2") (pintype "passive"))
      (node (ref "C6") (pin "2") (pinfunction "2_2") (pintype "passive"))
      (node (ref "D2") (pin "2") (pinfunction "K_2") (pintype "passive"))
      (node (ref "F1") (pin "2") (pinfunction "2_2") (pintype "passive"))
      (node (ref "H1") (pin "2") (pinfunction "2_2") (pintype "passive"))
      (node (ref "R23") (pin "1") (pinfunction "1_1") (pintype "passive"))
      (node (ref "R24") (pin "1") (pinfunction "1_1") (pintype "passive"))
      (node (ref "R25") (pin "1") (pinfunction "1_1") (pintype "passive"))
      (node (ref "R26") (pin "1") (pinfunction "1_1") (pintype "passive"))
      (node (ref "R27") (pin "1") (pinfunction "1_1") (pintype "passive"))
      (node (ref "U10") (pin "18") (pinfunction "AVCC_18") (pintype "passive"))
      (node (ref "U10") (pin "4") (pinfunction "VCC_4") (pintype "passive"))
      (node (ref "U10") (pin "6") (pinfunction "VCC_6") (pintype "passive"))
      (node (ref "U9") (pin "8") (pinfunction "VCC_8") (pintype "passive"))
    )
    (net (code "29") (name "8V3") (class "Default")
      (node (ref "C13") (pin "2") (pinfunction "2_2") (pintype "passive"))
      (node (ref "C17") (pin "1") (pinfunction "1_1") (pintype "passive"))
      (node (ref "C18") (pin "1") (pinfunction "1_1") (pintype "passive"))
      (node (ref "F3") (pin "2") (pinfunction "2_2") (pintype "passive"))
      (node (ref "R10") (pin "2") (pinfunction "2_2") (pintype "passive"))
      (node (ref "R15") (pin "1") (pinfunction "1_1") (pintype "passive"))
      (node (ref "R19") (pin "2") (pinfunction "2_2") (pintype "passive"))
      (node (ref "R34") (pin "1") (pinfunction "1_1") (pintype "passive"))
      (node (ref "U8") (pin "6") (pinfunction "VDD_6") (pintype "passive"))
    )
    (net (code "30") (name "ADS_VCC") (class "Default")
      (node (ref "C28") (pin "2") (pinfunction "2_2") (pintype "passive"))
      (node (ref "C29") (pin "1") (pinfunction "1_1") (pintype "passive"))
      (node (ref "C30") (pin "2") (pinfunction "2_2") (pintype "passive"))
      (node (ref "F4") (pin "1") (pinfunction "1_1") (pintype "passive"))
      (node (ref "R28") (pin "1") (pinfunction "1_1") (pintype "passive"))
      (node (ref "R29") (pin "1") (pinfunction "1_1") (pintype "passive"))
      (node (ref "U11") (pin "8") (pinfunction "VDD_8") (pintype "passive"))
    )
    (net (code "31") (name "GNDA") (class "Default")
      (node (ref "C1") (pin "1") (pinfunction "1_1") (pintype "passive"))
      (node (ref "C10") (pin "1") (pinfunction "1_1") (pintype "passive"))
      (node (ref "C11") (pin "2") (pinfunction "2_2") (pintype "passive"))
      (node (ref "C12") (pin "1") (pinfunction "1_1") (pintype "passive"))
      (node (ref "C13") (pin "1") (pinfunction "1_1") (pintype "passive"))
      (node (ref "C14") (pin "1") (pinfunction "1_1") (pintype "passive"))
      (node (ref "C17") (pin "2") (pinfunction "2_2") (pintype "passive"))
      (node (ref "C18") (pin "2") (pinfunction "2_2") (pintype "passive"))
      (node (ref "C20") (pin "2") (pinfunction "2_2") (pintype "passive"))
      (node (ref "C28") (pin "1") (pinfunction "1_1") (pintype "passive"))
      (node (ref "C29") (pin "2") (pinfunction "2_2") (pintype "passive"))
      (node (ref "C3") (pin "1") (pinfunction "1_1") (pintype "passive"))
      (node (ref "C30") (pin "1") (pinfunction "1_1") (pintype "passive"))
      (node (ref "C31") (pin "1") (pinfunction "1_1") (pintype "passive"))
      (node (ref "C32") (pin "2") (pinfunction "2_2") (pintype "passive"))
      (node (ref "C4") (pin "1") (pinfunction "1_1") (pintype "passive"))
      (node (ref "C5") (pin "1") (pinfunction "1_1") (pintype "passive"))
      (node (ref "C7") (pin "1") (pinfunction "1_1") (pintype "passive"))
      (node (ref "C8") (pin "1") (pinfunction "1_1") (pintype "passive"))
      (node (ref "C9") (pin "1") (pinfunction "1_1") (pintype "passive"))
      (node (ref "F2") (pin "1") (pinfunction "1_1") (pintype "passive"))
      (node (ref "P1") (pin "5") (pinfunction "5_5") (pintype "passive"))
      (node (ref "Q1") (pin "2") (pinfunction "E_2") (pintype "passive"))
      (node (ref "Q2") (pin "2") (pinfunction "E_2") (pintype "passive"))
      (node (ref "R14") (pin "1") (pinfunction "1_1") (pintype "passive"))
      (node (ref "R18") (pin "2") (pinfunction "2_2") (pintype "passive"))
      (node (ref "R22") (pin "1") (pinfunction "1_1") (pintype "passive"))
      (node (ref "R31") (pin "1") (pinfunction "1_1") (pintype "passive"))
      (node (ref "R32") (pin "1") (pinfunction "1_1") (pintype "passive"))
      (node (ref "R6") (pin "1") (pinfunction "1_1") (pintype "passive"))
      (node (ref "R9") (pin "1") (pinfunction "1_1") (pintype "passive"))
      (node (ref "U1") (pin "3") (pinfunction "S/R-_3") (pintype "passive"))
      (node (ref "U1") (pin "4") (pinfunction "GND_4") (pintype "passive"))
      (node (ref "U11") (pin "3") (pinfunction "GND_3") (pintype "passive"))
      (node (ref "U11") (pin "6") (pinfunction "A2_6") (pintype "passive"))
      (node (ref "U11") (pin "7") (pinfunction "A3_7") (pintype "passive"))
      (node (ref "U2") (pin "2") (pinfunction "GND_2") (pintype "power_in"))
      (node (ref "U3") (pin "4") (pinfunction "V-_4") (pintype "power_in"))
      (node (ref "U4") (pin "4") (pinfunction "V-_4") (pintype "power_in"))
      (node (ref "U5") (pin "2") (pinfunction "-V_2") (pintype "passive"))
      (node (ref "U7") (pin "1") (pinfunction "S1_1") (pintype "passive"))
      (node (ref "U8") (pin "3") (pinfunction "GND_3") (pintype "passive"))
    )
    (net (code "32") (name "GNDD") (class "Default")
      (node (ref "C21") (pin "1") (pinfunction "1_1") (pintype "passive"))
      (node (ref "C22") (pin "1") (pinfunction "1_1") (pintype "passive"))
      (node (ref "C23") (pin "1") (pinfunction "1_1") (pintype "passive"))
      (node (ref "C24") (pin "1") (pinfunction "1_1") (pintype "passive"))
      (node (ref "C25") (pin "1") (pinfunction "1_1") (pintype "passive"))
      (node (ref "C26") (pin "1") (pinfunction "1_1") (pintype "passive"))
      (node (ref "C27") (pin "1") (pinfunction "1_1") (pintype "passive"))
      (node (ref "C6") (pin "1") (pinfunction "1_1") (pintype "passive"))
      (node (ref "D2") (pin "1") (pinfunction "A_1") (pintype "passive"))
      (node (ref "F2") (pin "2") (pinfunction "2_2") (pintype "passive"))
      (node (ref "H1") (pin "1") (pinfunction "1_1") (pintype "passive"))
      (node (ref "P1") (pin "3") (pinfunction "3_3") (pintype "passive"))
      (node (ref "R30") (pin "5") (pinfunction "5_5") (pintype "passive"))
      (node (ref "R30") (pin "6") (pinfunction "6_6") (pintype "passive"))
      (node (ref "R30") (pin "7") (pinfunction "7_7") (pintype "passive"))
      (node (ref "R30") (pin "8") (pinfunction "8_8") (pintype "passive"))
      (node (ref "U10") (pin "21") (pinfunction "GND_21") (pintype "passive"))
      (node (ref "U10") (pin "3") (pinfunction "GND_3") (pintype "passive"))
      (node (ref "U10") (pin "5") (pinfunction "GND_5") (pintype "passive"))
      (node (ref "U9") (pin "5") (pinfunction "GND_5") (pintype "passive"))
    )
    (net (code "33") (name "Net-(C15-Pad1)") (class "Default")
      (node (ref "C15") (pin "1") (pinfunction "1_1") (pintype "passive"))
      (node (ref "C16") (pin "1") (pinfunction "1_1") (pintype "passive"))
      (node (ref "C19") (pin "1") (pinfunction "1_1") (pintype "passive"))
      (node (ref "U7") (pin "5") (pinfunction "D2_5") (pintype "passive"))
      (node (ref "U7") (pin "6") (pinfunction "D2_6") (pintype "passive"))
      (node (ref "U7") (pin "7") (pinfunction "D1_7") (pintype "passive"))
      (node (ref "U7") (pin "8") (pinfunction "D1_8") (pintype "passive"))
    )
    (net (code "34") (name "Net-(P1-Pad1)") (class "Default")
      (node (ref "P1") (pin "1") (pinfunction "1_1") (pintype "passive"))
      (node (ref "R13") (pin "2") (pinfunction "2_2") (pintype "passive"))
    )
    (net (code "35") (name "Net-(P1-Pad2)") (class "Default")
      (node (ref "P1") (pin "2") (pinfunction "2_2") (pintype "passive"))
      (node (ref "R17") (pin "2") (pinfunction "2_2") (pintype "passive"))
    )
    (net (code "36") (name "Net-(Q1-B)") (class "Default")
      (node (ref "Q1") (pin "1") (pinfunction "B_1") (pintype "passive"))
      (node (ref "R12") (pin "2") (pinfunction "2_2") (pintype "passive"))
      (node (ref "R14") (pin "2") (pinfunction "2_2") (pintype "passive"))
    )
    (net (code "37") (name "Net-(Q2-B)") (class "Default")
      (node (ref "Q2") (pin "1") (pinfunction "B_1") (pintype "passive"))
      (node (ref "R21") (pin "2") (pinfunction "2_2") (pintype "passive"))
      (node (ref "R22") (pin "2") (pinfunction "2_2") (pintype "passive"))
    )
    (net (code "38") (name "Net-(R4-Pad2)") (class "Default")
      (node (ref "R4") (pin "2") (pinfunction "2_2") (pintype "passive"))
      (node (ref "U3") (pin "1") (pinfunction "OS_NUL_1") (pintype "passive"))
    )
    (net (code "39") (name "Net-(R5-BOT)") (class "Default")
      (node (ref "R2") (pin "1") (pinfunction "1_1") (pintype "passive"))
      (node (ref "R5") (pin "3") (pinfunction "BOT_3") (pintype "passive"))
    )
    (net (code "40") (name "Net-(R5-TAP)") (class "Default")
      (node (ref "R5") (pin "2") (pinfunction "TAP_2") (pintype "passive"))
      (node (ref "U4") (pin "3") (pinfunction "IN+_3") (pintype "input"))
    )
    (net (code "41") (name "Net-(R5-TOP)") (class "Default")
      (node (ref "R5") (pin "1") (pinfunction "TOP_1") (pintype "passive"))
      (node (ref "R6") (pin "2") (pinfunction "2_2") (pintype "passive"))
    )
    (net (code "42") (name "Net-(U1-Vbridge)") (class "Default")
      (node (ref "C7") (pin "2") (pinfunction "2_2") (pintype "passive"))
      (node (ref "R3") (pin "1") (pinfunction "1_1") (pintype "passive"))
      (node (ref "U1") (pin "7") (pinfunction "Vbridge_7") (pintype "passive"))
    )
    (net (code "43") (name "Net-(U3-TAB)") (class "Default")
      (node (ref "C2") (pin "2") (pinfunction "2_2") (pintype "passive"))
      (node (ref "R4") (pin "1") (pinfunction "1_1") (pintype "passive"))
      (node (ref "U3") (pin "8") (pinfunction "TAB_8") (pintype "passive"))
    )
    (net (code "44") (name "Net-(U5-+V)") (class "Default")
      (node (ref "R1") (pin "1") (pinfunction "1_1") (pintype "passive"))
      (node (ref "R2") (pin "2") (pinfunction "2_2") (pintype "passive"))
      (node (ref "U5") (pin "1") (pinfunction "+V_1") (pintype "passive"))
    )
    (net (code "45") (name "Net-(U6-ADJ)") (class "Default")
      (node (ref "R8") (pin "1") (pinfunction "1_1") (pintype "passive"))
      (node (ref "R9") (pin "2") (pinfunction "2_2") (pintype "passive"))
      (node (ref "U6") (pin "1") (pinfunction "ADJ_1") (pintype "input"))
    )
    (net (code "46") (name "Net-(U6-OUT)") (class "Default")
      (node (ref "C11") (pin "1") (pinfunction "1_1") (pintype "passive"))
      (node (ref "C12") (pin "2") (pinfunction "2_2") (pintype "passive"))
      (node (ref "F3") (pin "1") (pinfunction "1_1") (pintype "passive"))
      (node (ref "R34") (pin "2") (pinfunction "2_2") (pintype "passive"))
      (node (ref "R7") (pin "1") (pinfunction "1_1") (pintype "passive"))
      (node (ref "R8") (pin "2") (pinfunction "2_2") (pintype "passive"))
      (node (ref "U6") (pin "2") (pinfunction "OUT_2") (pintype "power_in"))
    )
    (net (code "47") (name "Net-(U7-G1)") (class "Default")
      (node (ref "R11") (pin "1") (pinfunction "1_1") (pintype "passive"))
      (node (ref "U7") (pin "2") (pinfunction "G1_2") (pintype "passive"))
    )
    (net (code "48") (name "Net-(U7-G2)") (class "Default")
      (node (ref "R20") (pin "1") (pinfunction "1_1") (pintype "passive"))
      (node (ref "U7") (pin "4") (pinfunction "G2_4") (pintype "passive"))
    )
    (net (code "49") (name "Net-(U7-S2)") (class "Default")
      (node (ref "C20") (pin "1") (pinfunction "1_1") (pintype "passive"))
      (node (ref "R15") (pin "2") (pinfunction "2_2") (pintype "passive"))
      (node (ref "U7") (pin "3") (pinfunction "S2_3") (pintype "passive"))
    )
    (net (code "50") (name "Net-(U10-AREF)") (class "Default")
      (node (ref "C27") (pin "2") (pinfunction "2_2") (pintype "passive"))
      (node (ref "U10") (pin "20") (pinfunction "AREF_20") (pintype "passive"))
    )
    (net (code "51") (name "Net-(U10-PC0_(ADC0{slash}PCINT8))") (class "Default")
      (node (ref "R24") (pin "2") (pinfunction "2_2") (pintype "passive"))
      (node (ref "R30") (pin "1") (pinfunction "1_1") (pintype "passive"))
      (node (ref "U10") (pin "23") (pinfunction "PC0_(ADC0/PCINT8)_23") (pintype "passive"))
    )
    (net (code "52") (name "Net-(U10-PC1_(ADC1{slash}PCINT9))") (class "Default")
      (node (ref "R25") (pin "2") (pinfunction "2_2") (pintype "passive"))
      (node (ref "R30") (pin "2") (pinfunction "2_2") (pintype "passive"))
      (node (ref "U10") (pin "24") (pinfunction "PC1_(ADC1/PCINT9)_24") (pintype "passive"))
    )
    (net (code "53") (name "Net-(U10-PC2_(ADC2{slash}PCINT10))") (class "Default")
      (node (ref "R26") (pin "2") (pinfunction "2_2") (pintype "passive"))
      (node (ref "R30") (pin "3") (pinfunction "3_3") (pintype "passive"))
      (node (ref "U10") (pin "25") (pinfunction "PC2_(ADC2/PCINT10)_25") (pintype "passive"))
    )
    (net (code "54") (name "Net-(U10-PC3_(ADC3{slash}PCINT11))") (class "Default")
      (node (ref "R27") (pin "2") (pinfunction "2_2") (pintype "passive"))
      (node (ref "R30") (pin "4") (pinfunction "4_4") (pintype "passive"))
      (node (ref "U10") (pin "26") (pinfunction "PC3_(ADC3/PCINT11)_26") (pintype "passive"))
    )
    (net (code "55") (name "Net-(U11-A0)") (class "Default")
      (node (ref "C32") (pin "1") (pinfunction "1_1") (pintype "passive"))
      (node (ref "R33") (pin "2") (pinfunction "2_2") (pintype "passive"))
      (node (ref "U11") (pin "4") (pinfunction "A0_4") (pintype "passive"))
    )
    (net (code "56") (name "Net-(U11-ADDR)") (class "Default")
      (node (ref "R31") (pin "2") (pinfunction "2_2") (pintype "passive"))
      (node (ref "U11") (pin "1") (pinfunction "ADDR_1") (pintype "passive"))
    )
    (net (code "57") (name "VCC_IN") (class "Default")
      (node (ref "C10") (pin "2") (pinfunction "2_2") (pintype "passive"))
      (node (ref "C14") (pin "2") (pinfunction "2_2") (pintype "passive"))
      (node (ref "C8") (pin "2") (pinfunction "2_2") (pintype "passive"))
      (node (ref "D1") (pin "2") (pinfunction "K_2") (pintype "passive"))
      (node (ref "P1") (pin "4") (pinfunction "4_4") (pintype "passive"))
      (node (ref "R7") (pin "2") (pinfunction "2_2") (pintype "passive"))
      (node (ref "U2") (pin "1") (pinfunction "IN_1") (pintype "power_in"))
      (node (ref "U6") (pin "3") (pinfunction "IN_3") (pintype "power_in"))
    )
    (net (code "58") (name "unconnected-(U4B-IN+-Pad5)") (class "Default")
      (node (ref "U4") (pin "5") (pinfunction "IN+_5") (pintype "input+no_connect"))
    )
    (net (code "59") (name "unconnected-(U4B-IN--Pad6)") (class "Default")
      (node (ref "U4") (pin "6") (pinfunction "IN-_6") (pintype "input+no_connect"))
    )
    (net (code "60") (name "unconnected-(U4B-OUT-Pad7)") (class "Default")
      (node (ref "U4") (pin "7") (pinfunction "OUT_7") (pintype "output+no_connect"))
    )
    (net (code "61") (name "unconnected-(U5-NC-Pad3)") (class "Default")
      (node (ref "U5") (pin "3") (pinfunction "NC_3") (pintype "passive+no_connect"))
    )
    (net (code "62") (name "unconnected-(U8-NC-Pad1)") (class "Default")
      (node (ref "U8") (pin "1") (pinfunction "NC_1") (pintype "passive+no_connect"))
    )
    (net (code "63") (name "unconnected-(U8-NC-Pad8)") (class "Default")
      (node (ref "U8") (pin "8") (pinfunction "NC_8") (pintype "passive+no_connect"))
    )
    (net (code "64") (name "unconnected-(U10-ADC6-Pad19)") (class "Default")
      (node (ref "U10") (pin "19") (pinfunction "ADC6_19") (pintype "passive+no_connect"))
    )
    (net (code "65") (name "unconnected-(U10-ADC7-Pad22)") (class "Default")
      (node (ref "U10") (pin "22") (pinfunction "ADC7_22") (pintype "passive+no_connect"))
    )
    (net (code "66") (name "unconnected-(U10-PB0_(PCINT0{slash}CLKO{slash}ICP1)-Pad12)") (class "Default")
      (node (ref "U10") (pin "12") (pinfunction "PB0_(PCINT0/CLKO/ICP1)_12") (pintype "passive+no_connect"))
    )
    (net (code "67") (name "unconnected-(U10-PB2_(PCINT2{slash}~{SS}{slash}OC1B)-Pad14)") (class "Default")
      (node (ref "U10") (pin "14") (pinfunction "PB2_(PCINT2/~{SS}/OC1B)_14") (pintype "passive+no_connect"))
    )
    (net (code "68") (name "unconnected-(U10-PD5_(PCINT21{slash}OC0B{slash}T1)-Pad9)") (class "Default")
      (node (ref "U10") (pin "9") (pinfunction "PD5_(PCINT21/OC0B/T1)_9") (pintype "passive+no_connect"))
    )
    (net (code "69") (name "unconnected-(U10-PD6_(PCINT22{slash}OC0A{slash}AIN0)-Pad10)") (class "Default")
      (node (ref "U10") (pin "10") (pinfunction "PD6_(PCINT22/OC0A/AIN0)_10") (pintype "passive+no_connect"))
    )
    (net (code "70") (name "unconnected-(U10-PD7_(PCINT23{slash}AIN1)-Pad11)") (class "Default")
      (node (ref "U10") (pin "11") (pinfunction "PD7_(PCINT23/AIN1)_11") (pintype "passive+no_connect"))
    )
  )
)
